# BOB_v1_01.net
KiCad netlist of a schematic drawn in EAGLE
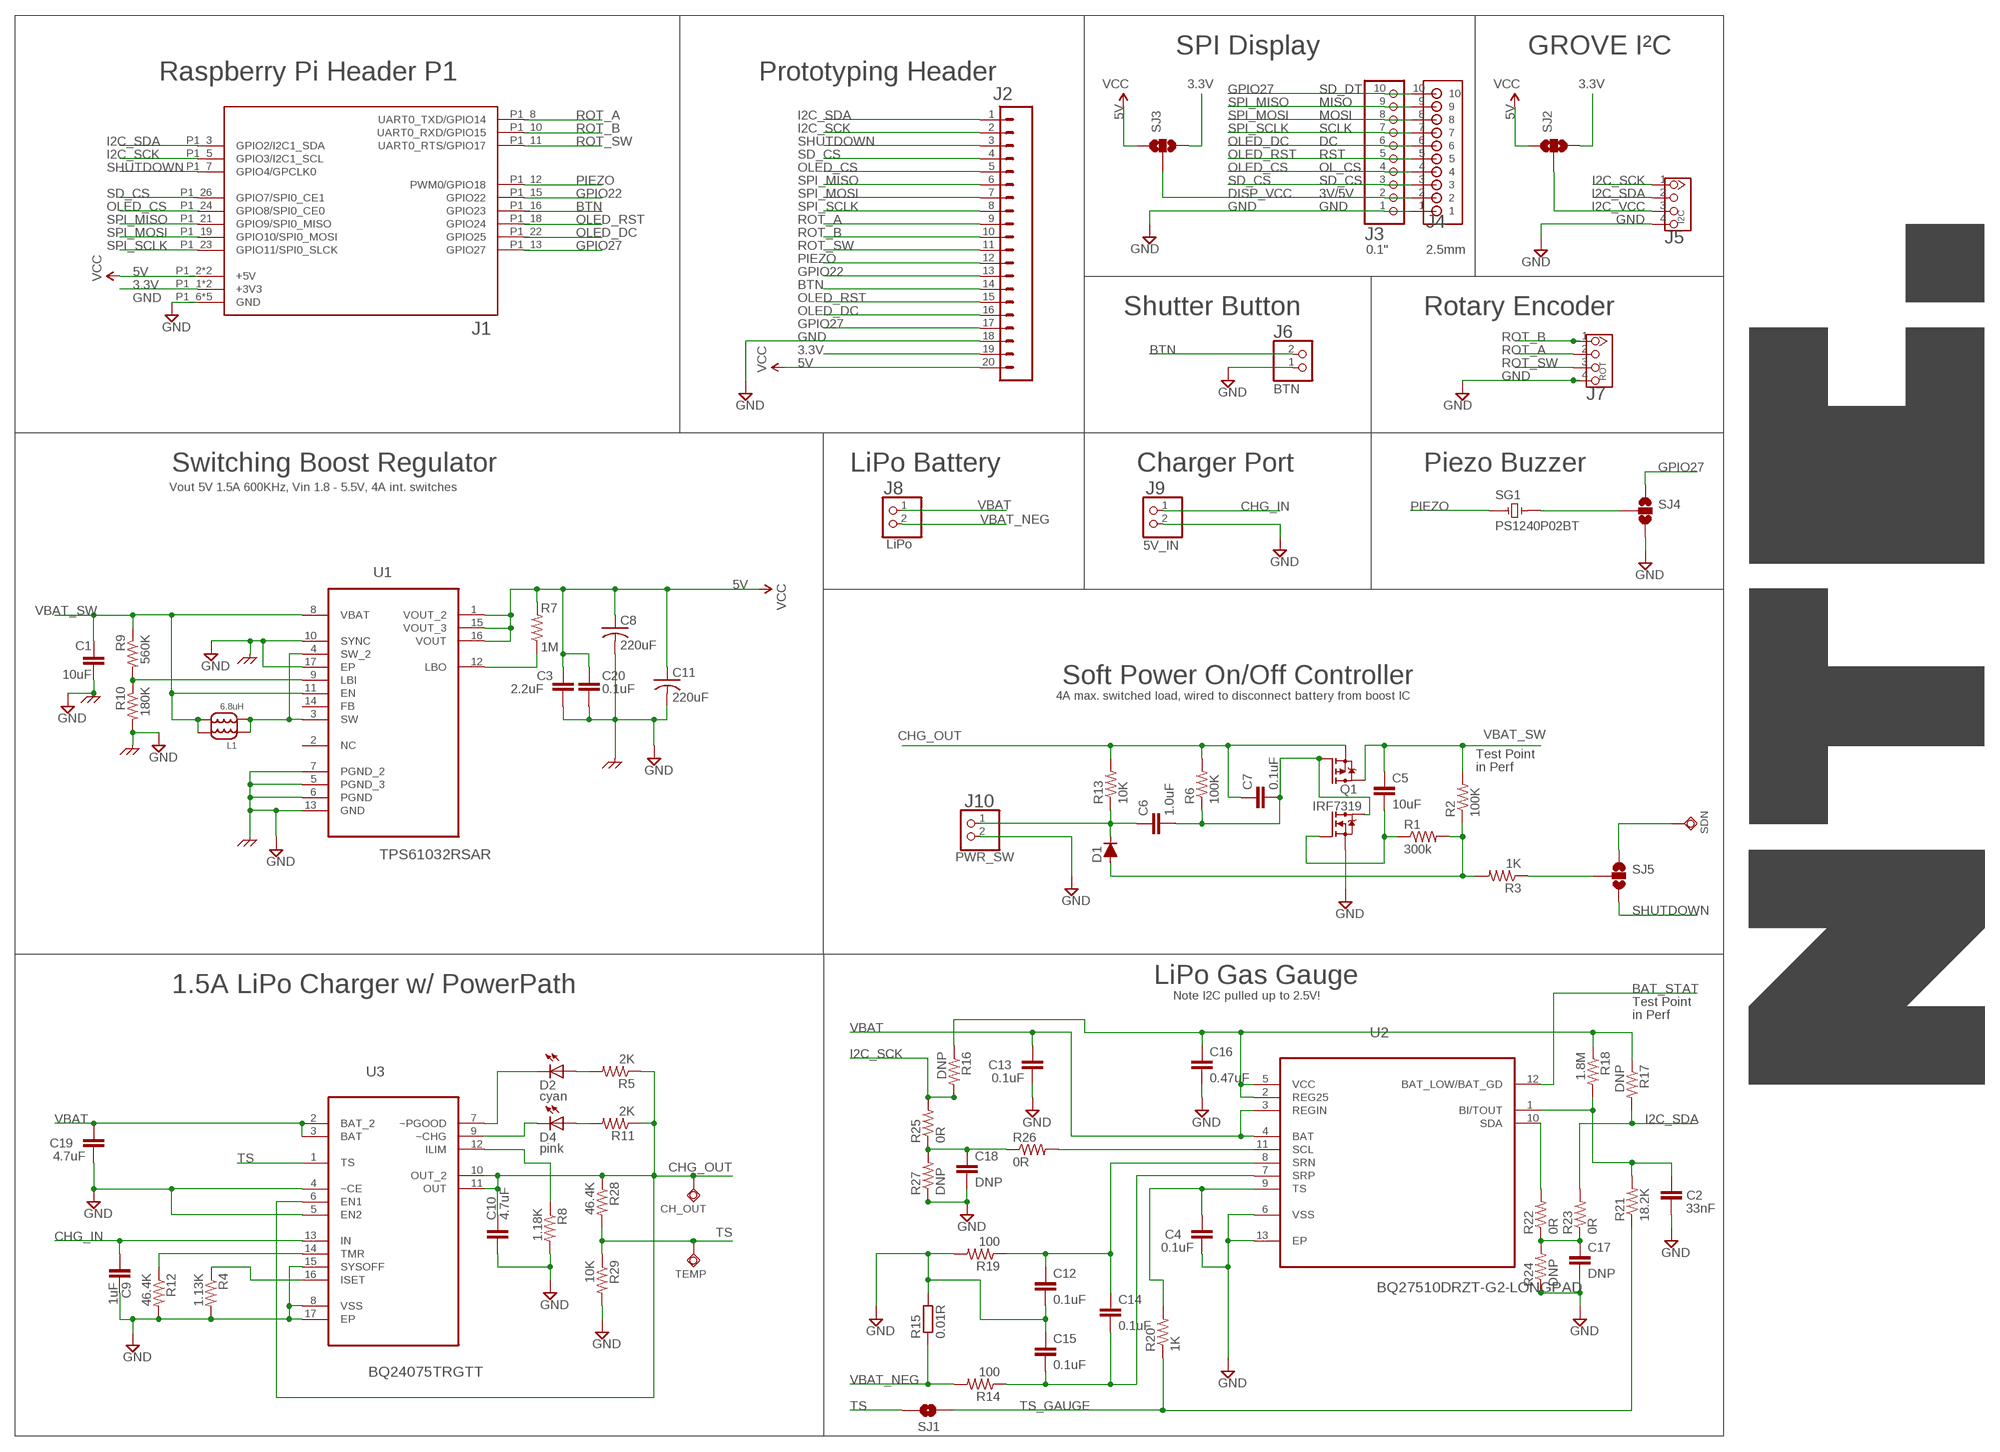
[diagram p0: schematic, sheet 1]

(export (version "E")
  (design (tool "Eeschema 10.0.6"))
  (components
    (comp (ref "C1")
      (value "10uF")
      (footprint "eagle-import:1206")
      (libsource (lib "eagle-import") (part "CAP1206"))
    )
    (comp (ref "C2")
      (value "33nF")
      (footprint "eagle-import:0603-CAP")
      (libsource (lib "eagle-import") (part "CAP0603-CAP"))
    )
    (comp (ref "C3")
      (value "2.2uF")
      (footprint "eagle-import:0603")
      (libsource (lib "eagle-import") (part "CAP0603"))
    )
    (comp (ref "C4")
      (value "0.1uF")
      (footprint "eagle-import:0603-CAP")
      (libsource (lib "eagle-import") (part "CAP0603-CAP"))
    )
    (comp (ref "C5")
      (value "10uF")
      (footprint "eagle-import:0603-CAP")
      (libsource (lib "eagle-import") (part "10UF-6.3V-20%(0603)"))
    )
    (comp (ref "C6")
      (value "1.0uF")
      (footprint "eagle-import:0603-CAP")
      (libsource (lib "eagle-import") (part "1.0UF-16V-10%(0603)"))
    )
    (comp (ref "C7")
      (value "0.1uF")
      (footprint "eagle-import:0603-CAP")
      (libsource (lib "eagle-import") (part "0.1UF-25V-5%(0603)"))
    )
    (comp (ref "C8")
      (value "220uF")
      (footprint "eagle-import:C1210")
      (libsource (lib "eagle-import") (part "C-USC1210"))
    )
    (comp (ref "C9")
      (value "1uF")
      (footprint "eagle-import:0603-CAP")
      (libsource (lib "eagle-import") (part "CAP0603-CAP"))
    )
    (comp (ref "C10")
      (value "4.7uF")
      (footprint "eagle-import:0603-CAP")
      (libsource (lib "eagle-import") (part "CAP0603-CAP"))
    )
    (comp (ref "C11")
      (value "220uF")
      (footprint "eagle-import:C1210")
      (libsource (lib "eagle-import") (part "C-USC1210"))
    )
    (comp (ref "C12")
      (value "0.1uF")
      (footprint "eagle-import:0603-CAP")
      (libsource (lib "eagle-import") (part "SparkFun-Capacitors_CAP0603-CAP"))
    )
    (comp (ref "C13")
      (value "0.1uF")
      (footprint "eagle-import:0603-CAP")
      (libsource (lib "eagle-import") (part "CAP0603-CAP"))
    )
    (comp (ref "C14")
      (value "0.1uF")
      (footprint "eagle-import:0603-CAP")
      (libsource (lib "eagle-import") (part "SparkFun-Capacitors_CAP0603-CAP"))
    )
    (comp (ref "C15")
      (value "0.1uF")
      (footprint "eagle-import:0603-CAP")
      (libsource (lib "eagle-import") (part "SparkFun-Capacitors_CAP0603-CAP"))
    )
    (comp (ref "C16")
      (value "0.47uF")
      (footprint "eagle-import:0603-CAP")
      (libsource (lib "eagle-import") (part "SparkFun-Capacitors_CAP0603-CAP"))
    )
    (comp (ref "C17")
      (value "DNP")
      (footprint "eagle-import:0603-CAP")
      (libsource (lib "eagle-import") (part "SparkFun-Capacitors_CAP0603-CAP"))
    )
    (comp (ref "C18")
      (value "DNP")
      (footprint "eagle-import:0603-CAP")
      (libsource (lib "eagle-import") (part "SparkFun-Capacitors_CAP0603-CAP"))
    )
    (comp (ref "C19")
      (value "4.7uF")
      (footprint "eagle-import:0603-CAP")
      (libsource (lib "eagle-import") (part "CAP0603-CAP"))
    )
    (comp (ref "C20")
      (value "0.1uF")
      (footprint "eagle-import:0603-CAP")
      (fields (field (name "PROD_ID") "CAP-00868"))
      (libsource (lib "eagle-import") (part "1.0UF-16V-10%(0603)"))
    )
    (comp (ref "CH_OUT")
      (value "TP1.2")
      (footprint "eagle-import:TP_1.2")
      (libsource (lib "eagle-import") (part "TP1.2"))
    )
    (comp (ref "D1")
      (value "D-FILL-SMB")
      (footprint "eagle-import:SMB")
      (libsource (lib "eagle-import") (part "D-FILL-SMB"))
    )
    (comp (ref "D2")
      (value "cyan")
      (footprint "eagle-import:LED-0603")
      (libsource (lib "eagle-import") (part "LED0603"))
    )
    (comp (ref "D4")
      (value "pink")
      (footprint "eagle-import:LED-0603")
      (libsource (lib "eagle-import") (part "LED0603"))
    )
    (comp (ref "J1")
      (value "PICAM_RPI-B-PICAM")
      (footprint "eagle-import:PICAM_RPI-B-PICAM")
      (libsource (lib "eagle-import") (part "PICAM_RPI-B-PICAM"))
    )
    (comp (ref "J2")
      (value "M20LOCK_LONGPADS")
      (footprint "eagle-import:1X20_LOCK_LONGPADS")
      (libsource (lib "eagle-import") (part "M20LOCK_LONGPADS"))
    )
    (comp (ref "J3")
      (value "PINHD-1X10")
      (footprint "eagle-import:1X10-BIG")
      (libsource (lib "eagle-import") (part "PINHD-1X10"))
    )
    (comp (ref "J4")
      (value "B10B-EH-A-RA")
      (footprint "eagle-import:S10B-EH")
      (libsource (lib "eagle-import") (part "B10B-EH-A-RA"))
    )
    (comp (ref "J5")
      (value "I2C")
      (footprint "eagle-import:4P-2.0")
      (libsource (lib "eagle-import") (part "TWIG-4P-2.0-2.0"))
    )
    (comp (ref "J6")
      (value "BTN")
      (footprint "eagle-import:PICAM_JST-PH-2-THM")
      (libsource (lib "eagle-import") (part "PICAM_JST_2PIN-THM"))
    )
    (comp (ref "J7")
      (value "ROT")
      (footprint "eagle-import:4P-2.0")
      (libsource (lib "eagle-import") (part "TWIG-4P-2.0-2.0"))
    )
    (comp (ref "J8")
      (value "LiPo")
      (footprint "eagle-import:PICAM_JST-PH-2-THM")
      (libsource (lib "eagle-import") (part "PICAM_JST_2PIN-THM"))
    )
    (comp (ref "J9")
      (value "5V_IN")
      (footprint "eagle-import:PICAM_JST-PH-2-THM")
      (libsource (lib "eagle-import") (part "PICAM_JST_2PIN-THM"))
    )
    (comp (ref "J10")
      (value "PWR_SW")
      (footprint "eagle-import:PICAM_JST-PH-2-THM")
      (libsource (lib "eagle-import") (part "PICAM_JST_2PIN-THM"))
    )
    (comp (ref "L1")
      (value "6.8uH")
      (footprint "eagle-import:SUMIDA_CDRH124")
      (libsource (lib "eagle-import") (part "SUMIDA_CDRH124CDRH124NP-6R8MC"))
    )
    (comp (ref "Q1")
      (value "IRF7319")
      (footprint "eagle-import:SO08-IRF")
      (libsource (lib "eagle-import") (part "IRF7319Q"))
    )
    (comp (ref "R1")
      (value "300k")
      (footprint "eagle-import:0603-RES")
      (libsource (lib "eagle-import") (part "SparkFun-Passives_RESISTOR0603-RES"))
    )
    (comp (ref "R2")
      (value "100K")
      (footprint "eagle-import:0603-RES")
      (libsource (lib "eagle-import") (part "SparkFun-Passives_RESISTOR0603-RES"))
    )
    (comp (ref "R3")
      (value "1K")
      (footprint "eagle-import:0603-RES")
      (libsource (lib "eagle-import") (part "SparkFun-Passives_RESISTOR0603-RES"))
    )
    (comp (ref "R4")
      (value "1.13K")
      (footprint "eagle-import:0603-RES")
      (libsource (lib "eagle-import") (part "RESISTOR0603-RES"))
    )
    (comp (ref "R5")
      (value "2K")
      (footprint "eagle-import:0603-RES")
      (libsource (lib "eagle-import") (part "RESISTOR0603-RES"))
    )
    (comp (ref "R6")
      (value "100K")
      (footprint "eagle-import:0603-RES")
      (libsource (lib "eagle-import") (part "SparkFun-Passives_RESISTOR0603-RES"))
    )
    (comp (ref "R7")
      (value "1M")
      (footprint "eagle-import:0603-RES")
      (libsource (lib "eagle-import") (part "RESISTOR0603-RES"))
    )
    (comp (ref "R8")
      (value "1.18K")
      (footprint "eagle-import:0603-RES")
      (libsource (lib "eagle-import") (part "RESISTOR0603-RES"))
    )
    (comp (ref "R9")
      (value "560K")
      (footprint "eagle-import:0603-RES")
      (libsource (lib "eagle-import") (part "RESISTOR0603-RES"))
    )
    (comp (ref "R10")
      (value "180K")
      (footprint "eagle-import:0603-RES")
      (libsource (lib "eagle-import") (part "RESISTOR0603-RES"))
    )
    (comp (ref "R11")
      (value "2K")
      (footprint "eagle-import:0603-RES")
      (libsource (lib "eagle-import") (part "RESISTOR0603-RES"))
    )
    (comp (ref "R12")
      (value "46.4K")
      (footprint "eagle-import:0603-RES")
      (libsource (lib "eagle-import") (part "RESISTOR0603-RES"))
    )
    (comp (ref "R13")
      (value "10K")
      (footprint "eagle-import:0603-RES")
      (libsource (lib "eagle-import") (part "SparkFun-Passives_RESISTOR0603-RES"))
    )
    (comp (ref "R14")
      (value "100")
      (footprint "eagle-import:0603-RES")
      (libsource (lib "eagle-import") (part "RESISTOR0603-RES"))
    )
    (comp (ref "R15")
      (value "0.01R")
      (footprint "eagle-import:R1206")
      (libsource (lib "eagle-import") (part "RESISTOR-1206"))
    )
    (comp (ref "R16")
      (value "DNP")
      (footprint "eagle-import:0603-RES")
      (libsource (lib "eagle-import") (part "RESISTOR0603-RES"))
    )
    (comp (ref "R17")
      (value "DNP")
      (footprint "eagle-import:0603-RES")
      (libsource (lib "eagle-import") (part "RESISTOR0603-RES"))
    )
    (comp (ref "R18")
      (value "1.8M")
      (footprint "eagle-import:0603-RES")
      (libsource (lib "eagle-import") (part "RESISTOR0603-RES"))
    )
    (comp (ref "R19")
      (value "100")
      (footprint "eagle-import:0603-RES")
      (libsource (lib "eagle-import") (part "RESISTOR0603-RES"))
    )
    (comp (ref "R20")
      (value "1K")
      (footprint "eagle-import:0603-RES")
      (libsource (lib "eagle-import") (part "SparkFun-Resistors_RESISTOR0603-RES"))
    )
    (comp (ref "R21")
      (value "18.2K")
      (footprint "eagle-import:0603-RES")
      (libsource (lib "eagle-import") (part "SparkFun-Resistors_RESISTOR0603-RES"))
    )
    (comp (ref "R22")
      (value "0R")
      (footprint "eagle-import:0603-RES")
      (libsource (lib "eagle-import") (part "SparkFun-Resistors_RESISTOR0603-RES"))
    )
    (comp (ref "R23")
      (value "0R")
      (footprint "eagle-import:0603-RES")
      (libsource (lib "eagle-import") (part "SparkFun-Resistors_RESISTOR0603-RES"))
    )
    (comp (ref "R24")
      (value "DNP")
      (footprint "eagle-import:0603-RES")
      (libsource (lib "eagle-import") (part "SparkFun-Resistors_RESISTOR0603-RES"))
    )
    (comp (ref "R25")
      (value "0R")
      (footprint "eagle-import:0603-RES")
      (libsource (lib "eagle-import") (part "SparkFun-Resistors_RESISTOR0603-RES"))
    )
    (comp (ref "R26")
      (value "0R")
      (footprint "eagle-import:0603-RES")
      (libsource (lib "eagle-import") (part "SparkFun-Resistors_RESISTOR0603-RES"))
    )
    (comp (ref "R27")
      (value "DNP")
      (footprint "eagle-import:0603-RES")
      (libsource (lib "eagle-import") (part "SparkFun-Resistors_RESISTOR0603-RES"))
    )
    (comp (ref "R28")
      (value "46.4K")
      (footprint "eagle-import:0603-RES")
      (libsource (lib "eagle-import") (part "RESISTOR0603-RES"))
    )
    (comp (ref "R29")
      (value "10K")
      (footprint "eagle-import:0603-RES")
      (libsource (lib "eagle-import") (part "RESISTOR0603-RES"))
    )
    (comp (ref "SDN")
      (value "TP1.2")
      (footprint "eagle-import:TP_1.2")
      (libsource (lib "eagle-import") (part "TP1.2"))
    )
    (comp (ref "SG1")
      (value "PS1240P02BT")
      (footprint "eagle-import:PS1240")
      (libsource (lib "eagle-import") (part "PS1240P02BT"))
    )
    (comp (ref "SJ1")
      (value "SOLDERJUMPER-OLDTRACE")
      (footprint "eagle-import:SJ_2S-TRACE")
      (libsource (lib "eagle-import") (part "SOLDERJUMPER-OLDTRACE"))
    )
    (comp (ref "SJ2")
      (value "SOLDERJUMPER_2WAYPASTE1&2")
      (footprint "eagle-import:SJ_3_PASTE1&2")
      (libsource (lib "eagle-import") (part "SOLDERJUMPER_2WAYPASTE1&2"))
    )
    (comp (ref "SJ3")
      (value "SOLDERJUMPER_2WAYPASTE2&3")
      (footprint "eagle-import:SJ_3_PASTE2&3")
      (libsource (lib "eagle-import") (part "SOLDERJUMPER_2WAYPASTE2&3"))
    )
    (comp (ref "SJ4")
      (value "SOLDERJUMPER_2WAYPASTE1&2")
      (footprint "eagle-import:SJ_3_PASTE1&2")
      (libsource (lib "eagle-import") (part "SOLDERJUMPER_2WAYPASTE1&2"))
    )
    (comp (ref "SJ5")
      (value "SOLDERJUMPER_2WAYPASTE2&3")
      (footprint "eagle-import:SJ_3_PASTE2&3")
      (libsource (lib "eagle-import") (part "SOLDERJUMPER_2WAYPASTE2&3"))
    )
    (comp (ref "TEMP")
      (value "TP1.2")
      (footprint "eagle-import:TP_1.2")
      (libsource (lib "eagle-import") (part "TP1.2"))
    )
    (comp (ref "U1")
      (value "TPS61032RSAR")
      (footprint "eagle-import:QFN65P400X400X100-17N")
      (libsource (lib "eagle-import") (part "TPS61032RSAR"))
    )
    (comp (ref "U2")
      (value "BQ27510DRZT-G2-LONGPAD")
      (footprint "eagle-import:SON40P400X250X100-13N+LONGPAD")
      (fields (field (name "MPN") "BQ27510DRZT-G2") (field (name "SUPPLIER") "Texas Inustruments"))
      (libsource (lib "eagle-import") (part "BQ27510DRZT-G2-LONGPAD"))
    )
    (comp (ref "U3")
      (value "BQ24075TRGTT")
      (footprint "eagle-import:QFN50P300X300X100-17N")
      (libsource (lib "eagle-import") (part "BQ24075TRGTT"))
    )
  )
  (nets
    (net (code "1") (name "3.3V") (class "Default")
      (node (ref "J1") (pin "P1_1") (pinfunction "+3V3_P1_1") (pintype "power_in"))
      (node (ref "J1") (pin "P1_17") (pinfunction "+3V3_P1_17") (pintype "power_in"))
      (node (ref "J2") (pin "19") (pinfunction "19_19") (pintype "passive"))
      (node (ref "SJ2") (pin "3") (pinfunction "3_3") (pintype "passive"))
      (node (ref "SJ3") (pin "3") (pinfunction "3_3") (pintype "passive"))
    )
    (net (code "2") (name "5V") (class "Default")
      (node (ref "C11") (pin "1") (pinfunction "1_1") (pintype "passive"))
      (node (ref "C20") (pin "1") (pinfunction "1_1") (pintype "passive"))
      (node (ref "C3") (pin "1") (pinfunction "1_1") (pintype "passive"))
      (node (ref "C8") (pin "1") (pinfunction "1_1") (pintype "passive"))
      (node (ref "J1") (pin "P1_2") (pinfunction "+5V_P1_2") (pintype "power_in"))
      (node (ref "J1") (pin "P1_4") (pinfunction "+5V_P1_4") (pintype "power_in"))
      (node (ref "J2") (pin "20") (pinfunction "20_20") (pintype "passive"))
      (node (ref "R7") (pin "2") (pinfunction "2_2") (pintype "passive"))
      (node (ref "SJ2") (pin "1") (pinfunction "1_1") (pintype "passive"))
      (node (ref "SJ3") (pin "1") (pinfunction "1_1") (pintype "passive"))
      (node (ref "U1") (pin "1") (pinfunction "VOUT_2_1") (pintype "output"))
      (node (ref "U1") (pin "15") (pinfunction "VOUT_3_15") (pintype "output"))
      (node (ref "U1") (pin "16") (pinfunction "VOUT_16") (pintype "output"))
    )
    (net (code "3") (name "BAT_STAT") (class "Default")
      (node (ref "U2") (pin "12") (pinfunction "BAT_LOW/BAT_GD_12") (pintype "output"))
    )
    (net (code "4") (name "BTN") (class "Default")
      (node (ref "J1") (pin "P1_16") (pinfunction "GPIO23_P1_16") (pintype "bidirectional"))
      (node (ref "J2") (pin "14") (pinfunction "14_14") (pintype "passive"))
      (node (ref "J6") (pin "2") (pinfunction "1_2") (pintype "passive"))
    )
    (net (code "5") (name "CHG_IN") (class "Default")
      (node (ref "C9") (pin "1") (pinfunction "1_1") (pintype "passive"))
      (node (ref "J9") (pin "1") (pinfunction "2_1") (pintype "passive"))
      (node (ref "U3") (pin "13") (pinfunction "IN_13") (pintype "input"))
    )
    (net (code "6") (name "CHG_OUT") (class "Default")
      (node (ref "C10") (pin "1") (pinfunction "1_1") (pintype "passive"))
      (node (ref "C7") (pin "1") (pinfunction "1_1") (pintype "passive"))
      (node (ref "CH_OUT") (pin "1") (pinfunction "TP_1") (pintype "passive"))
      (node (ref "Q1") (pin "3") (pinfunction "P-S2_3") (pintype "passive"))
      (node (ref "R11") (pin "1") (pinfunction "1_1") (pintype "passive"))
      (node (ref "R13") (pin "2") (pinfunction "2_2") (pintype "passive"))
      (node (ref "R28") (pin "1") (pinfunction "1_1") (pintype "passive"))
      (node (ref "R5") (pin "1") (pinfunction "1_1") (pintype "passive"))
      (node (ref "R6") (pin "2") (pinfunction "2_2") (pintype "passive"))
      (node (ref "U3") (pin "10") (pinfunction "OUT_2_10") (pintype "output"))
      (node (ref "U3") (pin "11") (pinfunction "OUT_11") (pintype "output"))
      (node (ref "U3") (pin "6") (pinfunction "EN1_6") (pintype "input"))
    )
    (net (code "7") (name "DISP_VCC") (class "Default")
      (node (ref "J3") (pin "2") (pinfunction "2_2") (pintype "passive"))
      (node (ref "J4") (pin "2") (pinfunction "2_2") (pintype "bidirectional"))
      (node (ref "SJ3") (pin "2") (pinfunction "2_2") (pintype "passive"))
    )
    (net (code "8") (name "GND") (class "Default")
      (node (ref "C1") (pin "2") (pinfunction "2_2") (pintype "passive"))
      (node (ref "C10") (pin "2") (pinfunction "2_2") (pintype "passive"))
      (node (ref "C11") (pin "2") (pinfunction "2_2") (pintype "passive"))
      (node (ref "C12") (pin "2") (pinfunction "2_2") (pintype "passive"))
      (node (ref "C13") (pin "2") (pinfunction "2_2") (pintype "passive"))
      (node (ref "C15") (pin "1") (pinfunction "1_1") (pintype "passive"))
      (node (ref "C16") (pin "2") (pinfunction "2_2") (pintype "passive"))
      (node (ref "C17") (pin "2") (pinfunction "2_2") (pintype "passive"))
      (node (ref "C18") (pin "2") (pinfunction "2_2") (pintype "passive"))
      (node (ref "C19") (pin "2") (pinfunction "2_2") (pintype "passive"))
      (node (ref "C2") (pin "2") (pinfunction "2_2") (pintype "passive"))
      (node (ref "C20") (pin "2") (pinfunction "2_2") (pintype "passive"))
      (node (ref "C3") (pin "2") (pinfunction "2_2") (pintype "passive"))
      (node (ref "C4") (pin "2") (pinfunction "2_2") (pintype "passive"))
      (node (ref "C8") (pin "2") (pinfunction "2_2") (pintype "passive"))
      (node (ref "C9") (pin "2") (pinfunction "2_2") (pintype "passive"))
      (node (ref "J1") (pin "P1_14") (pinfunction "GND_P1_14") (pintype "power_in"))
      (node (ref "J1") (pin "P1_20") (pinfunction "GND_P1_20") (pintype "power_in"))
      (node (ref "J1") (pin "P1_25") (pinfunction "GND_P1_25") (pintype "power_in"))
      (node (ref "J1") (pin "P1_6") (pinfunction "GND_P1_6") (pintype "power_in"))
      (node (ref "J1") (pin "P1_9") (pinfunction "GND_P1_9") (pintype "power_in"))
      (node (ref "J10") (pin "2") (pinfunction "1_2") (pintype "passive"))
      (node (ref "J2") (pin "18") (pinfunction "18_18") (pintype "passive"))
      (node (ref "J3") (pin "1") (pinfunction "1_1") (pintype "passive"))
      (node (ref "J4") (pin "1") (pinfunction "1_1") (pintype "bidirectional"))
      (node (ref "J5") (pin "4") (pinfunction "4_4") (pintype "bidirectional"))
      (node (ref "J6") (pin "1") (pinfunction "2_1") (pintype "passive"))
      (node (ref "J7") (pin "4") (pinfunction "4_4") (pintype "bidirectional"))
      (node (ref "J9") (pin "2") (pinfunction "1_2") (pintype "passive"))
      (node (ref "Q1") (pin "1") (pinfunction "N-S1_1") (pintype "passive"))
      (node (ref "R10") (pin "2") (pinfunction "2_2") (pintype "passive"))
      (node (ref "R12") (pin "2") (pinfunction "2_2") (pintype "passive"))
      (node (ref "R15") (pin "2") (pinfunction "2_2") (pintype "passive"))
      (node (ref "R19") (pin "2") (pinfunction "2_2") (pintype "passive"))
      (node (ref "R24") (pin "1") (pinfunction "1_1") (pintype "passive"))
      (node (ref "R27") (pin "1") (pinfunction "1_1") (pintype "passive"))
      (node (ref "R29") (pin "2") (pinfunction "2_2") (pintype "passive"))
      (node (ref "R4") (pin "2") (pinfunction "2_2") (pintype "passive"))
      (node (ref "R8") (pin "2") (pinfunction "2_2") (pintype "passive"))
      (node (ref "SJ4") (pin "3") (pinfunction "3_3") (pintype "passive"))
      (node (ref "U1") (pin "10") (pinfunction "SYNC_10") (pintype "input"))
      (node (ref "U1") (pin "13") (pinfunction "GND_13") (pintype "passive"))
      (node (ref "U1") (pin "17") (pinfunction "EP_17") (pintype "passive"))
      (node (ref "U1") (pin "5") (pinfunction "PGND_3_5") (pintype "passive"))
      (node (ref "U1") (pin "6") (pinfunction "PGND_6") (pintype "passive"))
      (node (ref "U1") (pin "7") (pinfunction "PGND_2_7") (pintype "passive"))
      (node (ref "U2") (pin "13") (pinfunction "EP_13") (pintype "passive"))
      (node (ref "U2") (pin "6") (pinfunction "VSS_6") (pintype "power_in"))
      (node (ref "U3") (pin "15") (pinfunction "SYSOFF_15") (pintype "input"))
      (node (ref "U3") (pin "17") (pinfunction "EP_17") (pintype "passive"))
      (node (ref "U3") (pin "4") (pinfunction "~{CE}_4") (pintype "input"))
      (node (ref "U3") (pin "5") (pinfunction "EN2_5") (pintype "input"))
      (node (ref "U3") (pin "8") (pinfunction "VSS_8") (pintype "passive"))
    )
    (net (code "9") (name "GPIO22") (class "Default")
      (node (ref "J1") (pin "P1_15") (pinfunction "GPIO22_P1_15") (pintype "bidirectional"))
      (node (ref "J2") (pin "13") (pinfunction "13_13") (pintype "passive"))
    )
    (net (code "10") (name "GPIO27") (class "Default")
      (node (ref "J1") (pin "P1_13") (pinfunction "GPIO27_P1_13") (pintype "bidirectional"))
      (node (ref "J2") (pin "17") (pinfunction "17_17") (pintype "passive"))
      (node (ref "J3") (pin "10") (pinfunction "10_10") (pintype "passive"))
      (node (ref "J4") (pin "10") (pinfunction "10_10") (pintype "bidirectional"))
      (node (ref "SJ4") (pin "1") (pinfunction "1_1") (pintype "passive"))
    )
    (net (code "11") (name "I2C_SCK") (class "Default")
      (node (ref "J1") (pin "P1_5") (pinfunction "GPIO3/I2C1_SCL_P1_5") (pintype "bidirectional"))
      (node (ref "J2") (pin "2") (pinfunction "2_2") (pintype "passive"))
      (node (ref "J5") (pin "1") (pinfunction "1_1") (pintype "bidirectional"))
      (node (ref "R16") (pin "2") (pinfunction "2_2") (pintype "passive"))
      (node (ref "R25") (pin "2") (pinfunction "2_2") (pintype "passive"))
    )
    (net (code "12") (name "I2C_SDA") (class "Default")
      (node (ref "J1") (pin "P1_3") (pinfunction "GPIO2/I2C1_SDA_P1_3") (pintype "bidirectional"))
      (node (ref "J2") (pin "1") (pinfunction "1_1") (pintype "passive"))
      (node (ref "J5") (pin "2") (pinfunction "2_2") (pintype "bidirectional"))
      (node (ref "R17") (pin "2") (pinfunction "2_2") (pintype "passive"))
      (node (ref "R23") (pin "2") (pinfunction "2_2") (pintype "passive"))
    )
    (net (code "13") (name "I2C_VCC") (class "Default")
      (node (ref "J5") (pin "3") (pinfunction "3_3") (pintype "bidirectional"))
      (node (ref "SJ2") (pin "2") (pinfunction "2_2") (pintype "passive"))
    )
    (net (code "14") (name "Net-(C17-Pad1)") (class "Default")
      (node (ref "C17") (pin "1") (pinfunction "1_1") (pintype "passive"))
      (node (ref "R22") (pin "1") (pinfunction "1_1") (pintype "passive"))
      (node (ref "R23") (pin "1") (pinfunction "1_1") (pintype "passive"))
      (node (ref "R24") (pin "2") (pinfunction "2_2") (pintype "passive"))
    )
    (net (code "15") (name "Net-(C18-Pad1)") (class "Default")
      (node (ref "C18") (pin "1") (pinfunction "1_1") (pintype "passive"))
      (node (ref "R25") (pin "1") (pinfunction "1_1") (pintype "passive"))
      (node (ref "R26") (pin "1") (pinfunction "1_1") (pintype "passive"))
      (node (ref "R27") (pin "2") (pinfunction "2_2") (pintype "passive"))
    )
    (net (code "16") (name "Net-(D1-A)") (class "Default")
      (node (ref "D1") (pin "2") (pinfunction "A_2") (pintype "passive"))
      (node (ref "R1") (pin "2") (pinfunction "2_2") (pintype "passive"))
      (node (ref "R2") (pin "1") (pinfunction "1_1") (pintype "passive"))
      (node (ref "R3") (pin "2") (pinfunction "2_2") (pintype "passive"))
    )
    (net (code "17") (name "Net-(D1-C)") (class "Default")
      (node (ref "C6") (pin "1") (pinfunction "1_1") (pintype "passive"))
      (node (ref "D1") (pin "1") (pinfunction "C_1") (pintype "passive"))
      (node (ref "J10") (pin "1") (pinfunction "2_1") (pintype "passive"))
      (node (ref "R13") (pin "1") (pinfunction "1_1") (pintype "passive"))
    )
    (net (code "18") (name "Net-(D2-PadA)") (class "Default")
      (node (ref "D2") (pin "A") (pinfunction "A_A") (pintype "passive"))
      (node (ref "R5") (pin "2") (pinfunction "2_2") (pintype "passive"))
    )
    (net (code "19") (name "Net-(D4-PadA)") (class "Default")
      (node (ref "D4") (pin "A") (pinfunction "A_A") (pintype "passive"))
      (node (ref "R11") (pin "2") (pinfunction "2_2") (pintype "passive"))
    )
    (net (code "20") (name "Net-(Q1-N-G1)") (class "Default")
      (node (ref "C5") (pin "2") (pinfunction "2_2") (pintype "passive"))
      (node (ref "Q1") (pin "2") (pinfunction "N-G1_2") (pintype "passive"))
      (node (ref "R1") (pin "1") (pinfunction "1_1") (pintype "passive"))
    )
    (net (code "21") (name "Net-(Q1-P-G2)") (class "Default")
      (node (ref "C6") (pin "2") (pinfunction "2_2") (pintype "passive"))
      (node (ref "C7") (pin "2") (pinfunction "2_2") (pintype "passive"))
      (node (ref "Q1") (pin "4") (pinfunction "P-G2_4") (pintype "passive"))
      (node (ref "Q1") (pin "7") (pinfunction "N-D1_7") (pintype "passive"))
      (node (ref "Q1") (pin "8") (pinfunction "N-D1_8") (pintype "passive"))
      (node (ref "R6") (pin "1") (pinfunction "1_1") (pintype "passive"))
    )
    (net (code "22") (name "Net-(R3-Pad1)") (class "Default")
      (node (ref "R3") (pin "1") (pinfunction "1_1") (pintype "passive"))
      (node (ref "SJ5") (pin "2") (pinfunction "2_2") (pintype "passive"))
    )
    (net (code "23") (name "Net-(SDN-TP)") (class "Default")
      (node (ref "SDN") (pin "1") (pinfunction "TP_1") (pintype "passive"))
      (node (ref "SJ5") (pin "1") (pinfunction "1_1") (pintype "passive"))
    )
    (net (code "24") (name "Net-(SG1-2)") (class "Default")
      (node (ref "SG1") (pin "P$2") (pinfunction "2_P$2") (pintype "passive"))
      (node (ref "SJ4") (pin "2") (pinfunction "2_2") (pintype "passive"))
    )
    (net (code "25") (name "Net-(U1-LBI)") (class "Default")
      (node (ref "R10") (pin "1") (pinfunction "1_1") (pintype "passive"))
      (node (ref "R9") (pin "2") (pinfunction "2_2") (pintype "passive"))
      (node (ref "U1") (pin "9") (pinfunction "LBI_9") (pintype "input"))
    )
    (net (code "26") (name "Net-(U1-LBO)") (class "Default")
      (node (ref "R7") (pin "1") (pinfunction "1_1") (pintype "passive"))
      (node (ref "U1") (pin "12") (pinfunction "LBO_12") (pintype "output"))
    )
    (net (code "27") (name "Net-(U1-SW)") (class "Default")
      (node (ref "L1") (pin "P$3") (pinfunction "2_P$3") (pintype "passive"))
      (node (ref "L1") (pin "P$4") (pinfunction "2_P$4") (pintype "passive"))
      (node (ref "U1") (pin "3") (pinfunction "SW_3") (pintype "input"))
      (node (ref "U1") (pin "4") (pinfunction "SW_2_4") (pintype "input"))
    )
    (net (code "28") (name "Net-(U2-BI{slash}TOUT)") (class "Default")
      (node (ref "C2") (pin "1") (pinfunction "1_1") (pintype "passive"))
      (node (ref "R18") (pin "2") (pinfunction "2_2") (pintype "passive"))
      (node (ref "R21") (pin "2") (pinfunction "2_2") (pintype "passive"))
      (node (ref "U2") (pin "1") (pinfunction "BI/TOUT_1") (pintype "bidirectional"))
    )
    (net (code "29") (name "Net-(U2-REG25)") (class "Default")
      (node (ref "C16") (pin "1") (pinfunction "1_1") (pintype "passive"))
      (node (ref "R16") (pin "1") (pinfunction "1_1") (pintype "passive"))
      (node (ref "R17") (pin "1") (pinfunction "1_1") (pintype "passive"))
      (node (ref "R18") (pin "1") (pinfunction "1_1") (pintype "passive"))
      (node (ref "U2") (pin "2") (pinfunction "REG25_2") (pintype "power_in"))
      (node (ref "U2") (pin "5") (pinfunction "VCC_5") (pintype "power_in"))
    )
    (net (code "30") (name "Net-(U2-SCL)") (class "Default")
      (node (ref "R26") (pin "2") (pinfunction "2_2") (pintype "passive"))
      (node (ref "U2") (pin "11") (pinfunction "SCL_11") (pintype "input"))
    )
    (net (code "31") (name "Net-(U2-SDA)") (class "Default")
      (node (ref "R22") (pin "2") (pinfunction "2_2") (pintype "passive"))
      (node (ref "U2") (pin "10") (pinfunction "SDA_10") (pintype "bidirectional"))
    )
    (net (code "32") (name "Net-(U2-SRN)") (class "Default")
      (node (ref "C12") (pin "1") (pinfunction "1_1") (pintype "passive"))
      (node (ref "C14") (pin "1") (pinfunction "1_1") (pintype "passive"))
      (node (ref "R19") (pin "1") (pinfunction "1_1") (pintype "passive"))
      (node (ref "U2") (pin "8") (pinfunction "SRN_8") (pintype "input"))
    )
    (net (code "33") (name "Net-(U2-SRP)") (class "Default")
      (node (ref "C14") (pin "2") (pinfunction "2_2") (pintype "passive"))
      (node (ref "C15") (pin "2") (pinfunction "2_2") (pintype "passive"))
      (node (ref "R14") (pin "1") (pinfunction "1_1") (pintype "passive"))
      (node (ref "U2") (pin "7") (pinfunction "SRP_7") (pintype "input"))
    )
    (net (code "34") (name "Net-(U2-TS)") (class "Default")
      (node (ref "C4") (pin "1") (pinfunction "1_1") (pintype "passive"))
      (node (ref "R20") (pin "2") (pinfunction "2_2") (pintype "passive"))
      (node (ref "U2") (pin "9") (pinfunction "TS_9") (pintype "input"))
    )
    (net (code "35") (name "Net-(U3-ILIM)") (class "Default")
      (node (ref "R8") (pin "1") (pinfunction "1_1") (pintype "passive"))
      (node (ref "U3") (pin "12") (pinfunction "ILIM_12") (pintype "output"))
    )
    (net (code "36") (name "Net-(U3-ISET)") (class "Default")
      (node (ref "R4") (pin "1") (pinfunction "1_1") (pintype "passive"))
      (node (ref "U3") (pin "16") (pinfunction "ISET_16") (pintype "bidirectional"))
    )
    (net (code "37") (name "Net-(U3-TMR)") (class "Default")
      (node (ref "R12") (pin "1") (pinfunction "1_1") (pintype "passive"))
      (node (ref "U3") (pin "14") (pinfunction "TMR_14") (pintype "input"))
    )
    (net (code "38") (name "Net-(U3-~{CHG})") (class "Default")
      (node (ref "D4") (pin "C") (pinfunction "C_C") (pintype "passive"))
      (node (ref "U3") (pin "9") (pinfunction "~{CHG}_9") (pintype "output"))
    )
    (net (code "39") (name "Net-(U3-~{PGOOD})") (class "Default")
      (node (ref "D2") (pin "C") (pinfunction "C_C") (pintype "passive"))
      (node (ref "U3") (pin "7") (pinfunction "~{PGOOD}_7") (pintype "output"))
    )
    (net (code "40") (name "OLED_CS") (class "Default")
      (node (ref "J1") (pin "P1_24") (pinfunction "GPIO8/SPI0_CE0_P1_24") (pintype "bidirectional"))
      (node (ref "J2") (pin "5") (pinfunction "5_5") (pintype "passive"))
      (node (ref "J3") (pin "4") (pinfunction "4_4") (pintype "passive"))
      (node (ref "J4") (pin "4") (pinfunction "4_4") (pintype "bidirectional"))
    )
    (net (code "41") (name "OLED_DC") (class "Default")
      (node (ref "J1") (pin "P1_22") (pinfunction "GPIO25_P1_22") (pintype "bidirectional"))
      (node (ref "J2") (pin "16") (pinfunction "16_16") (pintype "passive"))
      (node (ref "J3") (pin "6") (pinfunction "6_6") (pintype "passive"))
      (node (ref "J4") (pin "6") (pinfunction "6_6") (pintype "bidirectional"))
    )
    (net (code "42") (name "OLED_RST") (class "Default")
      (node (ref "J1") (pin "P1_18") (pinfunction "GPIO24_P1_18") (pintype "bidirectional"))
      (node (ref "J2") (pin "15") (pinfunction "15_15") (pintype "passive"))
      (node (ref "J3") (pin "5") (pinfunction "5_5") (pintype "passive"))
      (node (ref "J4") (pin "5") (pinfunction "5_5") (pintype "bidirectional"))
    )
    (net (code "43") (name "PIEZO") (class "Default")
      (node (ref "J1") (pin "P1_12") (pinfunction "PWM0/GPIO18_P1_12") (pintype "bidirectional"))
      (node (ref "J2") (pin "12") (pinfunction "12_12") (pintype "passive"))
      (node (ref "SG1") (pin "P$1") (pinfunction "1_P$1") (pintype "passive"))
    )
    (net (code "44") (name "ROT_A") (class "Default")
      (node (ref "J1") (pin "P1_8") (pinfunction "UART0_TXD/GPIO14_P1_8") (pintype "bidirectional"))
      (node (ref "J2") (pin "9") (pinfunction "9_9") (pintype "passive"))
      (node (ref "J7") (pin "2") (pinfunction "2_2") (pintype "bidirectional"))
    )
    (net (code "45") (name "ROT_B") (class "Default")
      (node (ref "J1") (pin "P1_10") (pinfunction "UART0_RXD/GPIO15_P1_10") (pintype "bidirectional"))
      (node (ref "J2") (pin "10") (pinfunction "10_10") (pintype "passive"))
      (node (ref "J7") (pin "1") (pinfunction "1_1") (pintype "bidirectional"))
    )
    (net (code "46") (name "ROT_SW") (class "Default")
      (node (ref "J1") (pin "P1_11") (pinfunction "UART0_RTS/GPIO17_P1_11") (pintype "bidirectional"))
      (node (ref "J2") (pin "11") (pinfunction "11_11") (pintype "passive"))
      (node (ref "J7") (pin "3") (pinfunction "3_3") (pintype "bidirectional"))
    )
    (net (code "47") (name "SD_CS") (class "Default")
      (node (ref "J1") (pin "P1_26") (pinfunction "GPIO7/SPI0_CE1_P1_26") (pintype "bidirectional"))
      (node (ref "J2") (pin "4") (pinfunction "4_4") (pintype "passive"))
      (node (ref "J3") (pin "3") (pinfunction "3_3") (pintype "passive"))
      (node (ref "J4") (pin "3") (pinfunction "3_3") (pintype "bidirectional"))
    )
    (net (code "48") (name "SHUTDOWN") (class "Default")
      (node (ref "J1") (pin "P1_7") (pinfunction "GPIO4/GPCLK0_P1_7") (pintype "bidirectional"))
      (node (ref "J2") (pin "3") (pinfunction "3_3") (pintype "passive"))
      (node (ref "SJ5") (pin "3") (pinfunction "3_3") (pintype "passive"))
    )
    (net (code "49") (name "SPI_MISO") (class "Default")
      (node (ref "J1") (pin "P1_21") (pinfunction "GPIO9/SPI0_MISO_P1_21") (pintype "bidirectional"))
      (node (ref "J2") (pin "6") (pinfunction "6_6") (pintype "passive"))
      (node (ref "J3") (pin "9") (pinfunction "9_9") (pintype "passive"))
      (node (ref "J4") (pin "9") (pinfunction "9_9") (pintype "bidirectional"))
    )
    (net (code "50") (name "SPI_MOSI") (class "Default")
      (node (ref "J1") (pin "P1_19") (pinfunction "GPIO10/SPI0_MOSI_P1_19") (pintype "bidirectional"))
      (node (ref "J2") (pin "7") (pinfunction "7_7") (pintype "passive"))
      (node (ref "J3") (pin "8") (pinfunction "8_8") (pintype "passive"))
      (node (ref "J4") (pin "8") (pinfunction "8_8") (pintype "bidirectional"))
    )
    (net (code "51") (name "SPI_SCLK") (class "Default")
      (node (ref "J1") (pin "P1_23") (pinfunction "GPIO11/SPI0_SLCK_P1_23") (pintype "bidirectional"))
      (node (ref "J2") (pin "8") (pinfunction "8_8") (pintype "passive"))
      (node (ref "J3") (pin "7") (pinfunction "7_7") (pintype "passive"))
      (node (ref "J4") (pin "7") (pinfunction "7_7") (pintype "bidirectional"))
    )
    (net (code "52") (name "TS") (class "Default")
      (node (ref "R28") (pin "2") (pinfunction "2_2") (pintype "passive"))
      (node (ref "R29") (pin "1") (pinfunction "1_1") (pintype "passive"))
      (node (ref "SJ1") (pin "1") (pinfunction "1_1") (pintype "passive"))
      (node (ref "TEMP") (pin "1") (pinfunction "TP_1") (pintype "passive"))
      (node (ref "U3") (pin "1") (pinfunction "TS_1") (pintype "bidirectional"))
    )
    (net (code "53") (name "TS_GAUGE") (class "Default")
      (node (ref "R20") (pin "1") (pinfunction "1_1") (pintype "passive"))
      (node (ref "R21") (pin "1") (pinfunction "1_1") (pintype "passive"))
      (node (ref "SJ1") (pin "2") (pinfunction "2_2") (pintype "passive"))
    )
    (net (code "54") (name "VBAT") (class "Default")
      (node (ref "C13") (pin "1") (pinfunction "1_1") (pintype "passive"))
      (node (ref "C19") (pin "1") (pinfunction "1_1") (pintype "passive"))
      (node (ref "J8") (pin "1") (pinfunction "2_1") (pintype "passive"))
      (node (ref "U2") (pin "3") (pinfunction "REGIN_3") (pintype "power_in"))
      (node (ref "U2") (pin "4") (pinfunction "BAT_4") (pintype "input"))
      (node (ref "U3") (pin "2") (pinfunction "BAT_2_2") (pintype "bidirectional"))
      (node (ref "U3") (pin "3") (pinfunction "BAT_3") (pintype "bidirectional"))
    )
    (net (code "55") (name "VBAT_NEG") (class "Default")
      (node (ref "J8") (pin "2") (pinfunction "1_2") (pintype "passive"))
      (node (ref "R14") (pin "2") (pinfunction "2_2") (pintype "passive"))
      (node (ref "R15") (pin "1") (pinfunction "1_1") (pintype "passive"))
    )
    (net (code "56") (name "VBAT_SW") (class "Default")
      (node (ref "C1") (pin "1") (pinfunction "1_1") (pintype "passive"))
      (node (ref "C5") (pin "1") (pinfunction "1_1") (pintype "passive"))
      (node (ref "L1") (pin "P$1") (pinfunction "1_P$1") (pintype "passive"))
      (node (ref "L1") (pin "P$2") (pinfunction "1_P$2") (pintype "passive"))
      (node (ref "Q1") (pin "5") (pinfunction "P-D2_5") (pintype "passive"))
      (node (ref "Q1") (pin "6") (pinfunction "P-D2_6") (pintype "passive"))
      (node (ref "R2") (pin "2") (pinfunction "2_2") (pintype "passive"))
      (node (ref "R9") (pin "1") (pinfunction "1_1") (pintype "passive"))
      (node (ref "U1") (pin "11") (pinfunction "EN_11") (pintype "input"))
      (node (ref "U1") (pin "8") (pinfunction "VBAT_8") (pintype "input"))
    )
    (net (code "57") (name "unconnected-(U1-FB-Pad14)") (class "Default")
      (node (ref "U1") (pin "14") (pinfunction "FB_14") (pintype "input"))
    )
    (net (code "58") (name "unconnected-(U1-NC-Pad2)") (class "Default")
      (node (ref "U1") (pin "2") (pinfunction "NC_2") (pintype "no_connect"))
    )
  )
)
